# SCH_AIME_CARD_READER_STM32_2024-05-23.net
KiCad netlist of a schematic drawn in EasyEDA
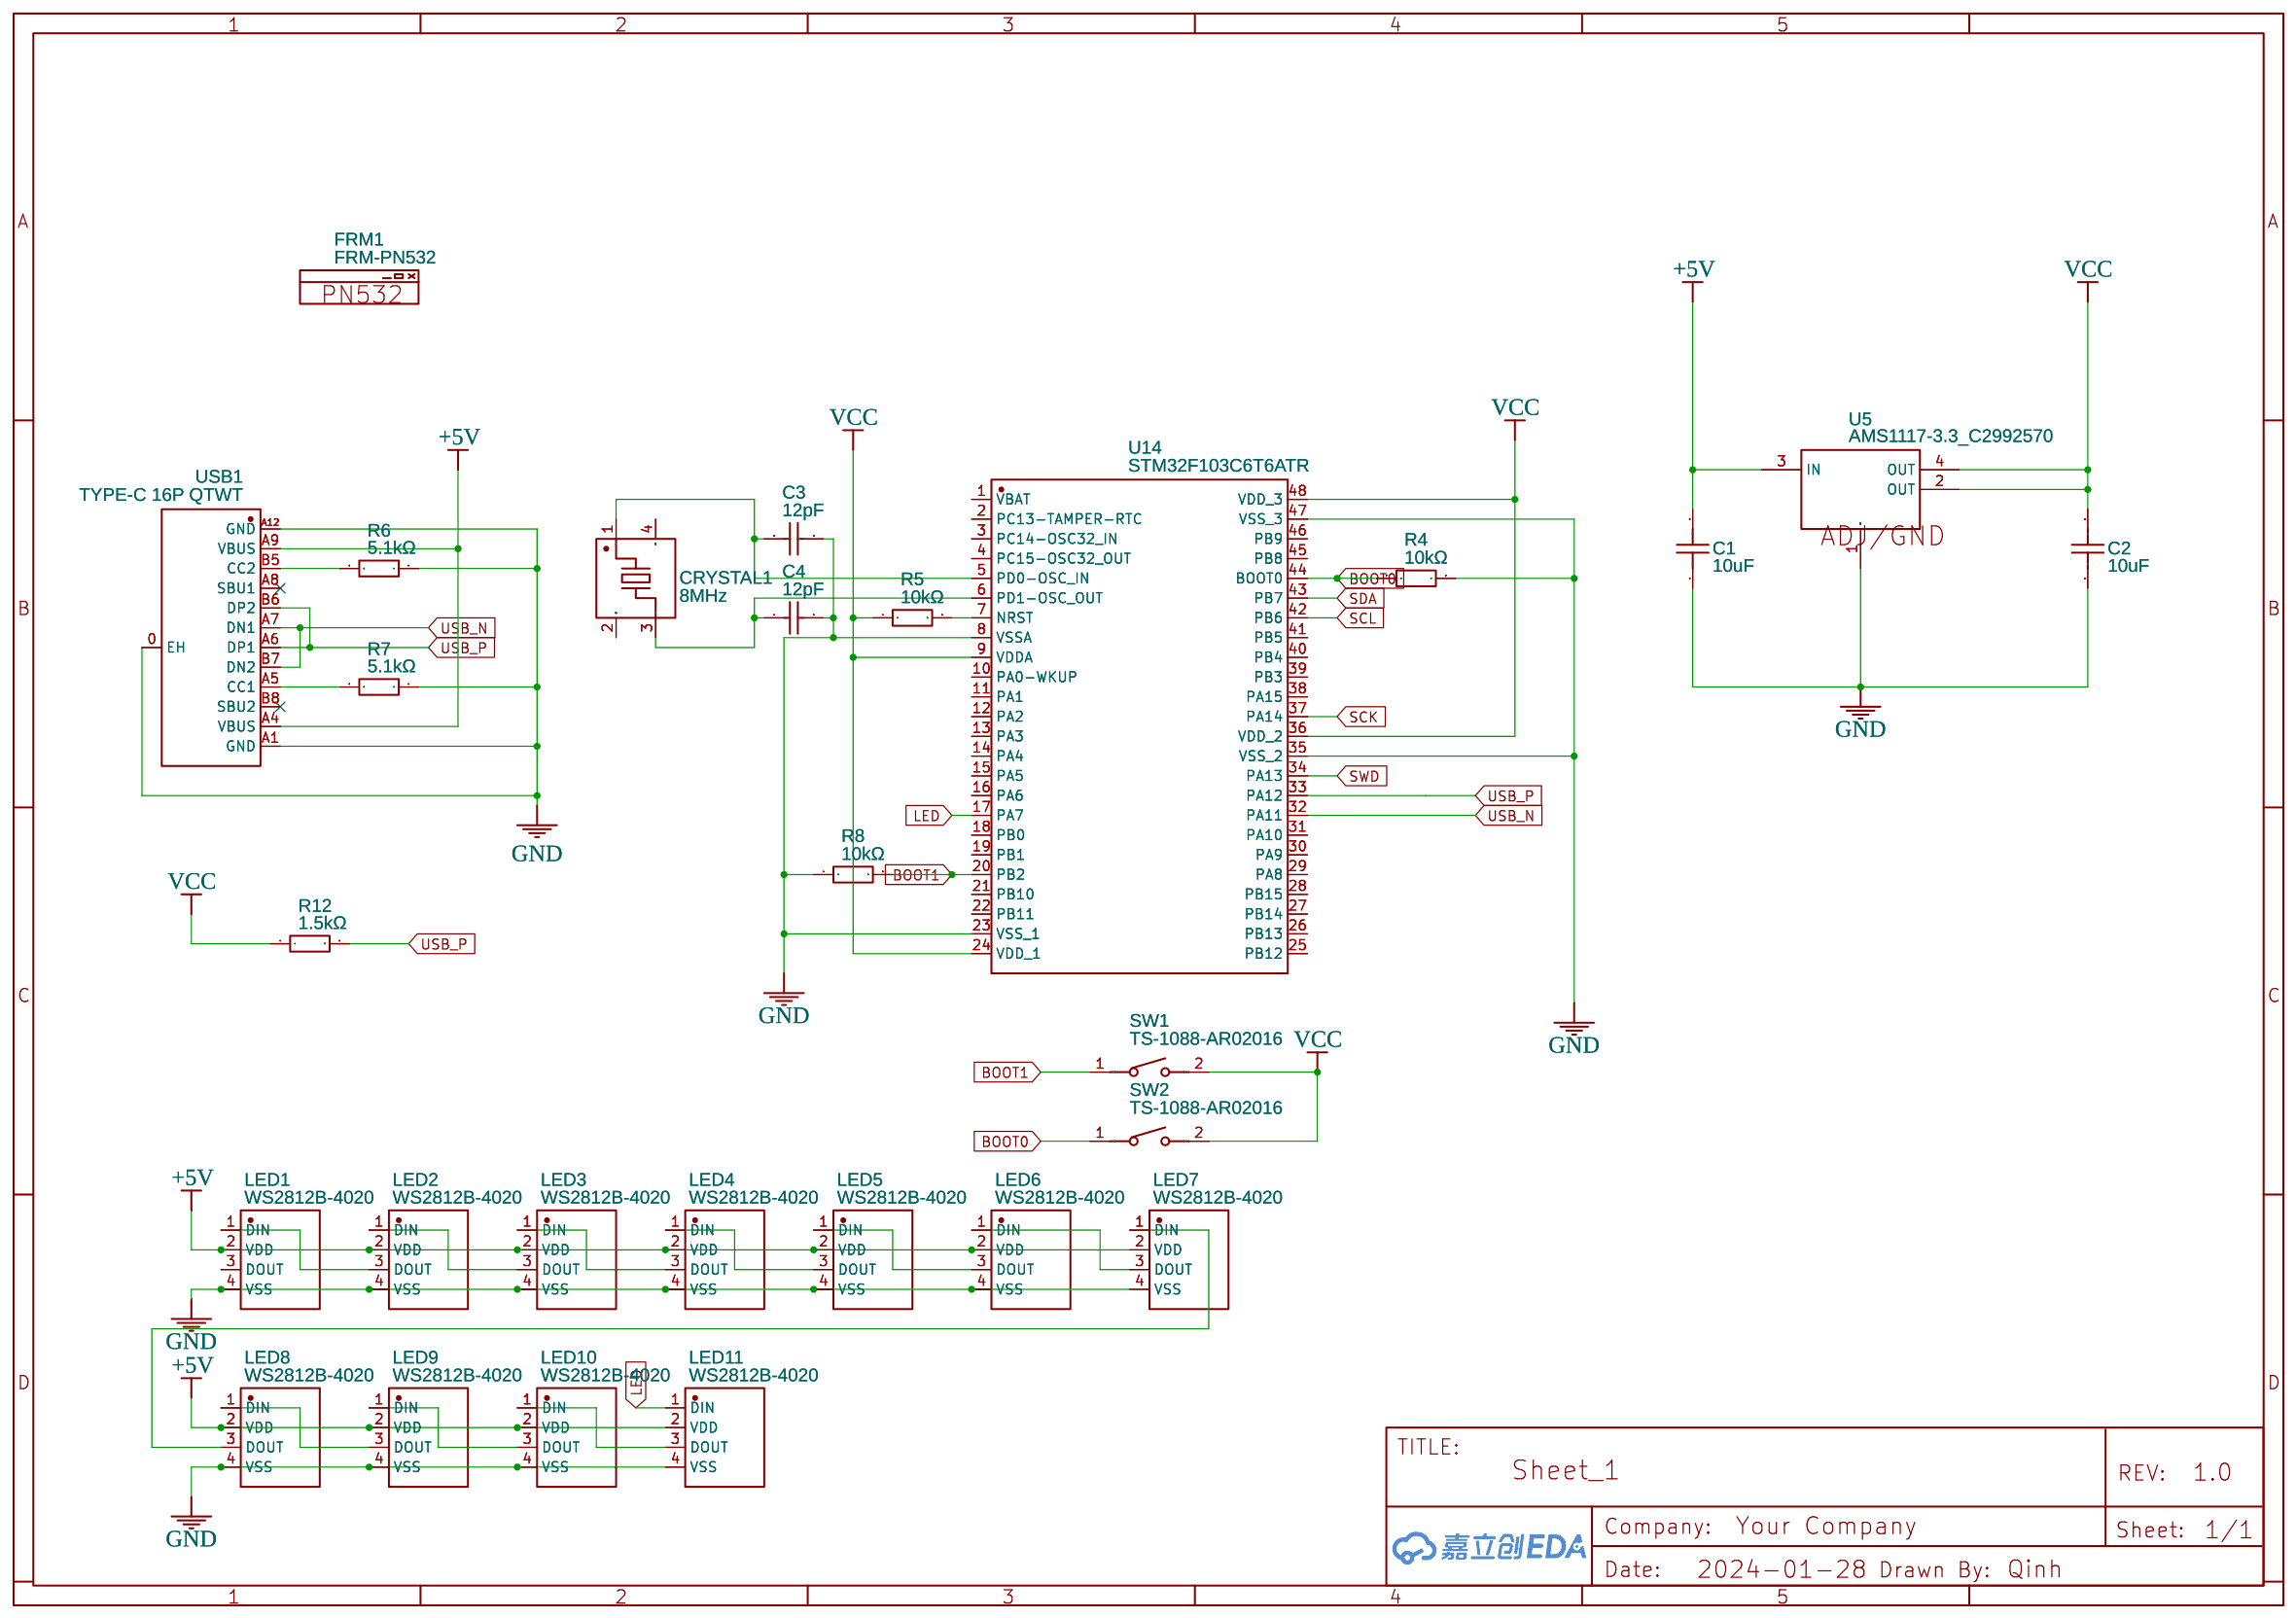
[diagram p0: schematic sheet]

(export (version "E")
  (design (tool "Eeschema 10.0.6"))
  (components
    (comp (ref "C1")
      (value "10uF")
      (fields
        (field (name "Manufacturer Part") "CL10A106KP8NNNC")
        (field (name "Manufacturer") "SAMSUNG(三星)")
      )
      (libsource (lib "") (part "CL10A106KP8NNNC"))
    )
    (comp (ref "C2")
      (value "10uF")
      (fields
        (field (name "Manufacturer Part") "CL10A106KP8NNNC")
        (field (name "Manufacturer") "SAMSUNG(三星)")
      )
      (libsource (lib "") (part "CL10A106KP8NNNC"))
    )
    (comp (ref "C3")
      (value "12pF")
      (fields
        (field (name "Manufacturer Part") "CL10C120JB8NNNC")
        (field (name "Manufacturer") "SAMSUNG(三星)")
      )
      (libsource (lib "") (part "CL10C120JB8NNNC"))
    )
    (comp (ref "C4")
      (value "12pF")
      (fields
        (field (name "Manufacturer Part") "CL10C120JB8NNNC")
        (field (name "Manufacturer") "SAMSUNG(三星)")
      )
      (libsource (lib "") (part "CL10C120JB8NNNC"))
    )
    (comp (ref "CRYSTAL1")
      (value "8MHz")
      (fields (field (name "Manufacturer Part") "CF4008M00012001") (field (name "Manufacturer") "HUAXIN(华昕)"))
      (libsource (lib "") (part "CF4008M00012001"))
    )
    (comp (ref "FRM1") (value "FRM-PN532") (libsource (lib "") (part "FRM-PN532")))
    (comp (ref "LED1")
      (value "WS2812B-4020")
      (fields (field (name "Manufacturer") "worldsemi"))
      (libsource (lib "") (part "WS2812B-4020"))
    )
    (comp (ref "LED2")
      (value "WS2812B-4020")
      (fields (field (name "Manufacturer") "worldsemi"))
      (libsource (lib "") (part "WS2812B-4020"))
    )
    (comp (ref "LED3")
      (value "WS2812B-4020")
      (fields (field (name "Manufacturer") "worldsemi"))
      (libsource (lib "") (part "WS2812B-4020"))
    )
    (comp (ref "LED4")
      (value "WS2812B-4020")
      (fields (field (name "Manufacturer") "worldsemi"))
      (libsource (lib "") (part "WS2812B-4020"))
    )
    (comp (ref "LED5")
      (value "WS2812B-4020")
      (fields (field (name "Manufacturer") "worldsemi"))
      (libsource (lib "") (part "WS2812B-4020"))
    )
    (comp (ref "LED6")
      (value "WS2812B-4020")
      (fields (field (name "Manufacturer") "worldsemi"))
      (libsource (lib "") (part "WS2812B-4020"))
    )
    (comp (ref "LED7")
      (value "WS2812B-4020")
      (fields (field (name "Manufacturer") "worldsemi"))
      (libsource (lib "") (part "WS2812B-4020"))
    )
    (comp (ref "LED8")
      (value "WS2812B-4020")
      (fields (field (name "Manufacturer") "worldsemi"))
      (libsource (lib "") (part "WS2812B-4020"))
    )
    (comp (ref "LED9")
      (value "WS2812B-4020")
      (fields (field (name "Manufacturer") "worldsemi"))
      (libsource (lib "") (part "WS2812B-4020"))
    )
    (comp (ref "LED10")
      (value "WS2812B-4020")
      (fields (field (name "Manufacturer") "worldsemi"))
      (libsource (lib "") (part "WS2812B-4020"))
    )
    (comp (ref "LED11")
      (value "WS2812B-4020")
      (fields (field (name "Manufacturer") "worldsemi"))
      (libsource (lib "") (part "WS2812B-4020"))
    )
    (comp (ref "R4")
      (value "10kΩ")
      (fields
        (field (name "Manufacturer Part") "0603WAF1002T5E")
        (field (name "Manufacturer") "UNI-ROYAL(厚声)")
      )
      (libsource (lib "") (part "0603WAF1002T5E"))
    )
    (comp (ref "R5")
      (value "10kΩ")
      (fields
        (field (name "Manufacturer Part") "0603WAF1002T5E")
        (field (name "Manufacturer") "UNI-ROYAL(厚声)")
      )
      (libsource (lib "") (part "0603WAF1002T5E"))
    )
    (comp (ref "R6")
      (value "5.1kΩ")
      (fields
        (field (name "BOM_Manufacturer Part") "RMC06035.1K1%N")
        (field (name "BOM_Supplier Part") "C269716")
      )
      (libsource (lib "") (part "RMC06035.1K1%N"))
    )
    (comp (ref "R7")
      (value "5.1kΩ")
      (fields
        (field (name "BOM_Manufacturer Part") "RMC06035.1K1%N")
        (field (name "BOM_Supplier Part") "C269716")
      )
      (libsource (lib "") (part "RMC06035.1K1%N"))
    )
    (comp (ref "R8")
      (value "10kΩ")
      (fields
        (field (name "Manufacturer Part") "0603WAF1002T5E")
        (field (name "Manufacturer") "UNI-ROYAL(厚声)")
      )
      (libsource (lib "") (part "0603WAF1002T5E"))
    )
    (comp (ref "R12")
      (value "1.5kΩ")
      (fields
        (field (name "Manufacturer Part") "0603WAF1501T5E")
        (field (name "Manufacturer") "UNI-ROYAL(厚声)")
      )
      (libsource (lib "") (part "0603WAF1501T5E"))
    )
    (comp (ref "SW1")
      (value "TS-1088-AR02016")
      (fields (field (name "Manufacturer") "XUNPU(讯普)"))
      (libsource (lib "") (part "TS-1088-AR02016"))
    )
    (comp (ref "SW2")
      (value "TS-1088-AR02016")
      (fields (field (name "Manufacturer") "XUNPU(讯普)"))
      (libsource (lib "") (part "TS-1088-AR02016"))
    )
    (comp (ref "U5")
      (value "AMS1117-3.3_C2992570")
      (fields
        (field (name "BOM_Manufacturer Part") "AMS1117-3.3")
        (field (name "BOM_Supplier Part") "C2992570")
      )
      (libsource (lib "") (part "AMS1117-3.3_C2992570"))
    )
    (comp (ref "U14")
      (value "STM32F103C6T6ATR")
      (fields (field (name "Manufacturer") "ST(意法半导体)"))
      (libsource (lib "") (part "STM32F103C6T6ATR"))
    )
    (comp (ref "USB1")
      (value "TYPE-C 16P QTWT")
      (fields (field (name "Manufacturer") "SHOU HAN(首韩)"))
      (libsource (lib "") (part "TYPE-C 16P QTWT"))
    )
  )
  (nets
    (net (code "1") (name "+5V") (class "Default")
      (node (ref "C1") (pin "2") (pinfunction "2_2") (pintype "unspecified"))
      (node (ref "LED1") (pin "2") (pinfunction "VDD_2") (pintype "unspecified"))
      (node (ref "LED10") (pin "2") (pinfunction "VDD_2") (pintype "unspecified"))
      (node (ref "LED11") (pin "2") (pinfunction "VDD_2") (pintype "unspecified"))
      (node (ref "LED2") (pin "2") (pinfunction "VDD_2") (pintype "unspecified"))
      (node (ref "LED3") (pin "2") (pinfunction "VDD_2") (pintype "unspecified"))
      (node (ref "LED4") (pin "2") (pinfunction "VDD_2") (pintype "unspecified"))
      (node (ref "LED5") (pin "2") (pinfunction "VDD_2") (pintype "unspecified"))
      (node (ref "LED6") (pin "2") (pinfunction "VDD_2") (pintype "unspecified"))
      (node (ref "LED7") (pin "2") (pinfunction "VDD_2") (pintype "unspecified"))
      (node (ref "LED8") (pin "2") (pinfunction "VDD_2") (pintype "unspecified"))
      (node (ref "LED9") (pin "2") (pinfunction "VDD_2") (pintype "unspecified"))
      (node (ref "U5") (pin "3") (pinfunction "IN_3") (pintype "passive"))
      (node (ref "USB1") (pin "A4") (pinfunction "VBUS_A4") (pintype "unspecified"))
      (node (ref "USB1") (pin "A9") (pinfunction "VBUS_A9") (pintype "unspecified"))
    )
    (net (code "2") (name "BOOT0") (class "Default")
      (node (ref "R4") (pin "1") (pinfunction "1_1") (pintype "input"))
      (node (ref "SW2") (pin "1") (pinfunction "1_1") (pintype "unspecified"))
      (node (ref "U14") (pin "44") (pinfunction "BOOT0_44") (pintype "unspecified"))
    )
    (net (code "3") (name "BOOT1") (class "Default")
      (node (ref "R8") (pin "2") (pinfunction "2_2") (pintype "input"))
      (node (ref "SW1") (pin "1") (pinfunction "1_1") (pintype "unspecified"))
      (node (ref "U14") (pin "20") (pinfunction "PB2_20") (pintype "unspecified"))
    )
    (net (code "4") (name "GND") (class "Default")
      (node (ref "C1") (pin "1") (pinfunction "1_1") (pintype "unspecified"))
      (node (ref "C2") (pin "1") (pinfunction "1_1") (pintype "unspecified"))
      (node (ref "C3") (pin "2") (pinfunction "2_2") (pintype "input"))
      (node (ref "C4") (pin "2") (pinfunction "2_2") (pintype "input"))
      (node (ref "LED1") (pin "4") (pinfunction "VSS_4") (pintype "unspecified"))
      (node (ref "LED10") (pin "4") (pinfunction "VSS_4") (pintype "unspecified"))
      (node (ref "LED11") (pin "4") (pinfunction "VSS_4") (pintype "unspecified"))
      (node (ref "LED2") (pin "4") (pinfunction "VSS_4") (pintype "unspecified"))
      (node (ref "LED3") (pin "4") (pinfunction "VSS_4") (pintype "unspecified"))
      (node (ref "LED4") (pin "4") (pinfunction "VSS_4") (pintype "unspecified"))
      (node (ref "LED5") (pin "4") (pinfunction "VSS_4") (pintype "unspecified"))
      (node (ref "LED6") (pin "4") (pinfunction "VSS_4") (pintype "unspecified"))
      (node (ref "LED7") (pin "4") (pinfunction "VSS_4") (pintype "unspecified"))
      (node (ref "LED8") (pin "4") (pinfunction "VSS_4") (pintype "unspecified"))
      (node (ref "LED9") (pin "4") (pinfunction "VSS_4") (pintype "unspecified"))
      (node (ref "R4") (pin "2") (pinfunction "2_2") (pintype "input"))
      (node (ref "R6") (pin "1") (pinfunction "1_1") (pintype "unspecified"))
      (node (ref "R7") (pin "1") (pinfunction "1_1") (pintype "unspecified"))
      (node (ref "R8") (pin "1") (pinfunction "1_1") (pintype "input"))
      (node (ref "U14") (pin "23") (pinfunction "VSS_1_23") (pintype "unspecified"))
      (node (ref "U14") (pin "35") (pinfunction "VSS_2_35") (pintype "unspecified"))
      (node (ref "U14") (pin "47") (pinfunction "VSS_3_47") (pintype "unspecified"))
      (node (ref "U14") (pin "8") (pinfunction "VSSA_8") (pintype "unspecified"))
      (node (ref "U5") (pin "1") (pinfunction "ADJ/GND_1") (pintype "passive"))
      (node (ref "USB1") (pin "0") (pinfunction "EH_0") (pintype "unspecified"))
      (node (ref "USB1") (pin "A1") (pinfunction "GND_A1") (pintype "unspecified"))
      (node (ref "USB1") (pin "A12") (pinfunction "GND_A12") (pintype "unspecified"))
    )
    (net (code "5") (name "LED") (class "Default")
      (node (ref "LED11") (pin "1") (pinfunction "DIN_1") (pintype "unspecified"))
      (node (ref "U14") (pin "17") (pinfunction "PA7_17") (pintype "unspecified"))
    )
    (net (code "6") (name "Net-(LED1-DIN)") (class "Default")
      (node (ref "LED1") (pin "1") (pinfunction "DIN_1") (pintype "unspecified"))
      (node (ref "LED2") (pin "3") (pinfunction "DOUT_3") (pintype "unspecified"))
    )
    (net (code "7") (name "Net-(LED2-DIN)") (class "Default")
      (node (ref "LED2") (pin "1") (pinfunction "DIN_1") (pintype "unspecified"))
      (node (ref "LED3") (pin "3") (pinfunction "DOUT_3") (pintype "unspecified"))
    )
    (net (code "8") (name "Net-(LED3-DIN)") (class "Default")
      (node (ref "LED3") (pin "1") (pinfunction "DIN_1") (pintype "unspecified"))
      (node (ref "LED4") (pin "3") (pinfunction "DOUT_3") (pintype "unspecified"))
    )
    (net (code "9") (name "Net-(LED4-DIN)") (class "Default")
      (node (ref "LED4") (pin "1") (pinfunction "DIN_1") (pintype "unspecified"))
      (node (ref "LED5") (pin "3") (pinfunction "DOUT_3") (pintype "unspecified"))
    )
    (net (code "10") (name "Net-(LED5-DIN)") (class "Default")
      (node (ref "LED5") (pin "1") (pinfunction "DIN_1") (pintype "unspecified"))
      (node (ref "LED6") (pin "3") (pinfunction "DOUT_3") (pintype "unspecified"))
    )
    (net (code "11") (name "Net-(LED6-DIN)") (class "Default")
      (node (ref "LED6") (pin "1") (pinfunction "DIN_1") (pintype "unspecified"))
      (node (ref "LED7") (pin "3") (pinfunction "DOUT_3") (pintype "unspecified"))
    )
    (net (code "12") (name "Net-(LED7-DIN)") (class "Default")
      (node (ref "LED7") (pin "1") (pinfunction "DIN_1") (pintype "unspecified"))
      (node (ref "LED8") (pin "3") (pinfunction "DOUT_3") (pintype "unspecified"))
    )
    (net (code "13") (name "Net-(LED8-DIN)") (class "Default")
      (node (ref "LED8") (pin "1") (pinfunction "DIN_1") (pintype "unspecified"))
      (node (ref "LED9") (pin "3") (pinfunction "DOUT_3") (pintype "unspecified"))
    )
    (net (code "14") (name "Net-(LED10-DIN)") (class "Default")
      (node (ref "LED10") (pin "1") (pinfunction "DIN_1") (pintype "unspecified"))
      (node (ref "LED11") (pin "3") (pinfunction "DOUT_3") (pintype "unspecified"))
    )
    (net (code "15") (name "Net-(LED10-DOUT)") (class "Default")
      (node (ref "LED10") (pin "3") (pinfunction "DOUT_3") (pintype "unspecified"))
      (node (ref "LED9") (pin "1") (pinfunction "DIN_1") (pintype "unspecified"))
    )
    (net (code "16") (name "Net-(U14-NRST)") (class "Default")
      (node (ref "R5") (pin "2") (pinfunction "2_2") (pintype "input"))
      (node (ref "U14") (pin "7") (pinfunction "NRST_7") (pintype "unspecified"))
    )
    (net (code "17") (name "Net-(U14-PD0-OSC_IN)") (class "Default")
      (node (ref "C3") (pin "1") (pinfunction "1_1") (pintype "input"))
      (node (ref "CRYSTAL1") (pin "1") (pinfunction "1_1") (pintype "input"))
      (node (ref "U14") (pin "5") (pinfunction "PD0-OSC_IN_5") (pintype "unspecified"))
    )
    (net (code "18") (name "Net-(U14-PD1-OSC_OUT)") (class "Default")
      (node (ref "C4") (pin "1") (pinfunction "1_1") (pintype "input"))
      (node (ref "CRYSTAL1") (pin "3") (pinfunction "3_3") (pintype "input"))
      (node (ref "U14") (pin "6") (pinfunction "PD1-OSC_OUT_6") (pintype "unspecified"))
    )
    (net (code "19") (name "Net-(USB1-CC1)") (class "Default")
      (node (ref "R7") (pin "2") (pinfunction "2_2") (pintype "unspecified"))
      (node (ref "USB1") (pin "A5") (pinfunction "CC1_A5") (pintype "unspecified"))
    )
    (net (code "20") (name "Net-(USB1-CC2)") (class "Default")
      (node (ref "R6") (pin "2") (pinfunction "2_2") (pintype "unspecified"))
      (node (ref "USB1") (pin "B5") (pinfunction "CC2_B5") (pintype "unspecified"))
    )
    (net (code "21") (name "SCK") (class "Default")
      (node (ref "U14") (pin "37") (pinfunction "PA14_37") (pintype "unspecified"))
    )
    (net (code "22") (name "SCL") (class "Default")
      (node (ref "U14") (pin "42") (pinfunction "PB6_42") (pintype "unspecified"))
    )
    (net (code "23") (name "SDA") (class "Default")
      (node (ref "U14") (pin "43") (pinfunction "PB7_43") (pintype "unspecified"))
    )
    (net (code "24") (name "SWD") (class "Default")
      (node (ref "U14") (pin "34") (pinfunction "PA13_34") (pintype "unspecified"))
    )
    (net (code "25") (name "USB_N") (class "Default")
      (node (ref "U14") (pin "32") (pinfunction "PA11_32") (pintype "unspecified"))
      (node (ref "USB1") (pin "A7") (pinfunction "DN1_A7") (pintype "unspecified"))
      (node (ref "USB1") (pin "B7") (pinfunction "DN2_B7") (pintype "unspecified"))
    )
    (net (code "26") (name "USB_P") (class "Default")
      (node (ref "R12") (pin "2") (pinfunction "2_2") (pintype "input"))
      (node (ref "U14") (pin "33") (pinfunction "PA12_33") (pintype "unspecified"))
      (node (ref "USB1") (pin "A6") (pinfunction "DP1_A6") (pintype "unspecified"))
      (node (ref "USB1") (pin "B6") (pinfunction "DP2_B6") (pintype "unspecified"))
    )
    (net (code "27") (name "VCC") (class "Default")
      (node (ref "C2") (pin "2") (pinfunction "2_2") (pintype "unspecified"))
      (node (ref "R12") (pin "1") (pinfunction "1_1") (pintype "input"))
      (node (ref "R5") (pin "1") (pinfunction "1_1") (pintype "input"))
      (node (ref "SW1") (pin "2") (pinfunction "2_2") (pintype "unspecified"))
      (node (ref "SW2") (pin "2") (pinfunction "2_2") (pintype "unspecified"))
      (node (ref "U14") (pin "24") (pinfunction "VDD_1_24") (pintype "unspecified"))
      (node (ref "U14") (pin "36") (pinfunction "VDD_2_36") (pintype "unspecified"))
      (node (ref "U14") (pin "48") (pinfunction "VDD_3_48") (pintype "unspecified"))
      (node (ref "U14") (pin "9") (pinfunction "VDDA_9") (pintype "unspecified"))
      (node (ref "U5") (pin "2") (pinfunction "OUT_2") (pintype "passive"))
      (node (ref "U5") (pin "4") (pinfunction "OUT_4") (pintype "passive"))
    )
    (net (code "28") (name "unconnected-(CRYSTAL1-GND-Pad2)") (class "Default")
      (node (ref "CRYSTAL1") (pin "2") (pinfunction "GND_2") (pintype "input"))
    )
    (net (code "29") (name "unconnected-(CRYSTAL1-GND-Pad4)") (class "Default")
      (node (ref "CRYSTAL1") (pin "4") (pinfunction "GND_4") (pintype "input"))
    )
    (net (code "30") (name "unconnected-(LED1-DOUT-Pad3)") (class "Default")
      (node (ref "LED1") (pin "3") (pinfunction "DOUT_3") (pintype "unspecified"))
    )
    (net (code "31") (name "unconnected-(U14-PA0-WKUP-Pad10)") (class "Default")
      (node (ref "U14") (pin "10") (pinfunction "PA0-WKUP_10") (pintype "unspecified"))
    )
    (net (code "32") (name "unconnected-(U14-PA1-Pad11)") (class "Default")
      (node (ref "U14") (pin "11") (pinfunction "PA1_11") (pintype "unspecified"))
    )
    (net (code "33") (name "unconnected-(U14-PA2-Pad12)") (class "Default")
      (node (ref "U14") (pin "12") (pinfunction "PA2_12") (pintype "unspecified"))
    )
    (net (code "34") (name "unconnected-(U14-PA3-Pad13)") (class "Default")
      (node (ref "U14") (pin "13") (pinfunction "PA3_13") (pintype "unspecified"))
    )
    (net (code "35") (name "unconnected-(U14-PA4-Pad14)") (class "Default")
      (node (ref "U14") (pin "14") (pinfunction "PA4_14") (pintype "unspecified"))
    )
    (net (code "36") (name "unconnected-(U14-PA5-Pad15)") (class "Default")
      (node (ref "U14") (pin "15") (pinfunction "PA5_15") (pintype "unspecified"))
    )
    (net (code "37") (name "unconnected-(U14-PA6-Pad16)") (class "Default")
      (node (ref "U14") (pin "16") (pinfunction "PA6_16") (pintype "unspecified"))
    )
    (net (code "38") (name "unconnected-(U14-PA8-Pad29)") (class "Default")
      (node (ref "U14") (pin "29") (pinfunction "PA8_29") (pintype "unspecified"))
    )
    (net (code "39") (name "unconnected-(U14-PA9-Pad30)") (class "Default")
      (node (ref "U14") (pin "30") (pinfunction "PA9_30") (pintype "unspecified"))
    )
    (net (code "40") (name "unconnected-(U14-PA10-Pad31)") (class "Default")
      (node (ref "U14") (pin "31") (pinfunction "PA10_31") (pintype "unspecified"))
    )
    (net (code "41") (name "unconnected-(U14-PA15-Pad38)") (class "Default")
      (node (ref "U14") (pin "38") (pinfunction "PA15_38") (pintype "unspecified"))
    )
    (net (code "42") (name "unconnected-(U14-PB0-Pad18)") (class "Default")
      (node (ref "U14") (pin "18") (pinfunction "PB0_18") (pintype "unspecified"))
    )
    (net (code "43") (name "unconnected-(U14-PB1-Pad19)") (class "Default")
      (node (ref "U14") (pin "19") (pinfunction "PB1_19") (pintype "unspecified"))
    )
    (net (code "44") (name "unconnected-(U14-PB3-Pad39)") (class "Default")
      (node (ref "U14") (pin "39") (pinfunction "PB3_39") (pintype "unspecified"))
    )
    (net (code "45") (name "unconnected-(U14-PB4-Pad40)") (class "Default")
      (node (ref "U14") (pin "40") (pinfunction "PB4_40") (pintype "unspecified"))
    )
    (net (code "46") (name "unconnected-(U14-PB5-Pad41)") (class "Default")
      (node (ref "U14") (pin "41") (pinfunction "PB5_41") (pintype "unspecified"))
    )
    (net (code "47") (name "unconnected-(U14-PB8-Pad45)") (class "Default")
      (node (ref "U14") (pin "45") (pinfunction "PB8_45") (pintype "unspecified"))
    )
    (net (code "48") (name "unconnected-(U14-PB9-Pad46)") (class "Default")
      (node (ref "U14") (pin "46") (pinfunction "PB9_46") (pintype "unspecified"))
    )
    (net (code "49") (name "unconnected-(U14-PB10-Pad21)") (class "Default")
      (node (ref "U14") (pin "21") (pinfunction "PB10_21") (pintype "unspecified"))
    )
    (net (code "50") (name "unconnected-(U14-PB11-Pad22)") (class "Default")
      (node (ref "U14") (pin "22") (pinfunction "PB11_22") (pintype "unspecified"))
    )
    (net (code "51") (name "unconnected-(U14-PB12-Pad25)") (class "Default")
      (node (ref "U14") (pin "25") (pinfunction "PB12_25") (pintype "unspecified"))
    )
    (net (code "52") (name "unconnected-(U14-PB13-Pad26)") (class "Default")
      (node (ref "U14") (pin "26") (pinfunction "PB13_26") (pintype "unspecified"))
    )
    (net (code "53") (name "unconnected-(U14-PB14-Pad27)") (class "Default")
      (node (ref "U14") (pin "27") (pinfunction "PB14_27") (pintype "unspecified"))
    )
    (net (code "54") (name "unconnected-(U14-PB15-Pad28)") (class "Default")
      (node (ref "U14") (pin "28") (pinfunction "PB15_28") (pintype "unspecified"))
    )
    (net (code "55") (name "unconnected-(U14-PC13-TAMPER-RTC-Pad2)") (class "Default")
      (node (ref "U14") (pin "2") (pinfunction "PC13-TAMPER-RTC_2") (pintype "unspecified"))
    )
    (net (code "56") (name "unconnected-(U14-PC14-OSC32_IN-Pad3)") (class "Default")
      (node (ref "U14") (pin "3") (pinfunction "PC14-OSC32_IN_3") (pintype "unspecified"))
    )
    (net (code "57") (name "unconnected-(U14-PC15-OSC32_OUT-Pad4)") (class "Default")
      (node (ref "U14") (pin "4") (pinfunction "PC15-OSC32_OUT_4") (pintype "unspecified"))
    )
    (net (code "58") (name "unconnected-(U14-VBAT-Pad1)") (class "Default")
      (node (ref "U14") (pin "1") (pinfunction "VBAT_1") (pintype "unspecified"))
    )
    (net (code "59") (name "unconnected-(USB1-SBU1-PadA8)") (class "Default")
      (node (ref "USB1") (pin "A8") (pinfunction "SBU1_A8") (pintype "unspecified+no_connect"))
    )
    (net (code "60") (name "unconnected-(USB1-SBU2-PadB8)") (class "Default")
      (node (ref "USB1") (pin "B8") (pinfunction "SBU2_B8") (pintype "unspecified+no_connect"))
    )
  )
)
